# avr_board.net
KiCad netlist of a schematic drawn in EAGLE
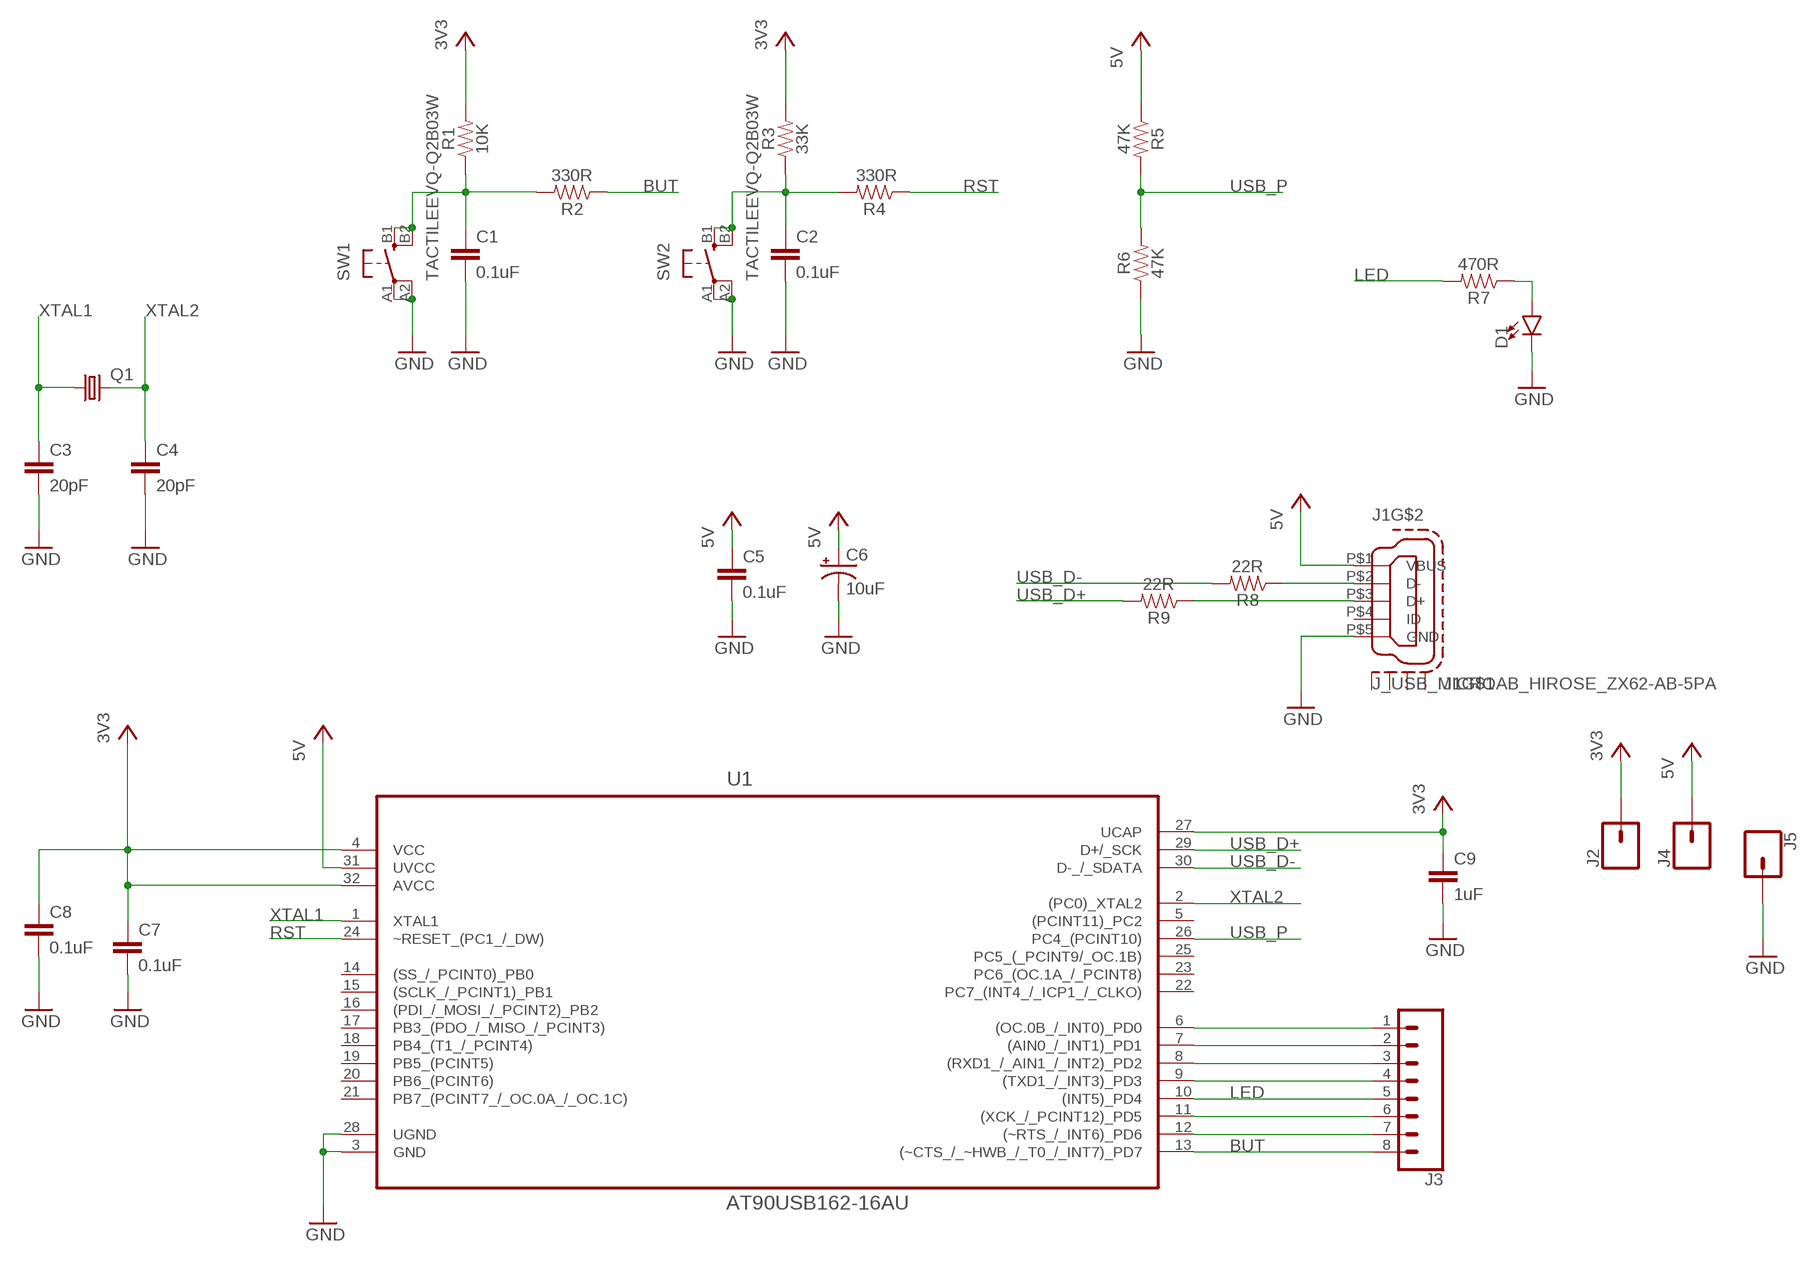
[diagram p0: schematic, sheet 1]

(export (version "E")
  (design (tool "Eeschema 10.0.6"))
  (components
    (comp (ref "C1")
      (value "0.1uF")
      (footprint "eagle-import:0603")
      (libsource (lib "eagle-import") (part "0.1UF-0603-25V-(+80/-20%)"))
    )
    (comp (ref "C2")
      (value "0.1uF")
      (footprint "eagle-import:0603")
      (libsource (lib "eagle-import") (part "0.1UF-0603-25V-(+80/-20%)"))
    )
    (comp (ref "C3")
      (value "20pF")
      (footprint "eagle-import:0603")
      (libsource (lib "eagle-import") (part "0.1UF-0603-25V-(+80/-20%)"))
    )
    (comp (ref "C4")
      (value "20pF")
      (footprint "eagle-import:0603")
      (libsource (lib "eagle-import") (part "0.1UF-0603-25V-(+80/-20%)"))
    )
    (comp (ref "C5")
      (value "0.1uF")
      (footprint "eagle-import:0603")
      (libsource (lib "eagle-import") (part "0.1UF-0603-25V-(+80/-20%)"))
    )
    (comp (ref "C6")
      (value "10uF")
      (footprint "eagle-import:EIA3216")
      (libsource (lib "eagle-import") (part "10UF-TANT"))
    )
    (comp (ref "C7")
      (value "0.1uF")
      (footprint "eagle-import:0603")
      (libsource (lib "eagle-import") (part "0.1UF-0603-25V-(+80/-20%)"))
    )
    (comp (ref "C8")
      (value "0.1uF")
      (footprint "eagle-import:0603")
      (libsource (lib "eagle-import") (part "0.1UF-0603-25V-(+80/-20%)"))
    )
    (comp (ref "C9")
      (value "1uF")
      (footprint "eagle-import:0603")
      (libsource (lib "eagle-import") (part "0.1UF-0603-25V-(+80/-20%)"))
    )
    (comp (ref "D1")
      (value "LEDPLCC")
      (footprint "eagle-import:PLCC-2")
      (libsource (lib "eagle-import") (part "LEDPLCC"))
    )
    (comp (ref "J1")
      (value "J_USB_MICROAB_HIROSE_ZX62-AB-5PA")
      (footprint "eagle-import:J_USB_MICROAB_HIROSE_ZX62-AB-5PA")
      (libsource (lib "eagle-import") (part "J_USB_MICROAB_HIROSE_ZX62-AB-5PA"))
    )
    (comp (ref "J2")
      (value "CONN_01")
      (footprint "eagle-import:1X01")
      (libsource (lib "eagle-import") (part "CONN_01"))
    )
    (comp (ref "J3")
      (value "CONN_08\"")
      (footprint "eagle-import:1X08")
      (libsource (lib "eagle-import") (part "CONN_08{dblquote}"))
    )
    (comp (ref "J4")
      (value "CONN_01")
      (footprint "eagle-import:1X01")
      (libsource (lib "eagle-import") (part "CONN_01"))
    )
    (comp (ref "J5")
      (value "CONN_01")
      (footprint "eagle-import:1X01")
      (libsource (lib "eagle-import") (part "CONN_01"))
    )
    (comp (ref "Q1")
      (value "CRYSTALCTS406")
      (footprint "eagle-import:CTS406")
      (libsource (lib "eagle-import") (part "CRYSTALCTS406"))
    )
    (comp (ref "R1")
      (value "10K")
      (footprint "eagle-import:0603")
      (libsource (lib "eagle-import") (part "RESISTOR0603"))
    )
    (comp (ref "R2")
      (value "330R")
      (footprint "eagle-import:0603")
      (libsource (lib "eagle-import") (part "RESISTOR0603"))
    )
    (comp (ref "R3")
      (value "33K")
      (footprint "eagle-import:0603")
      (libsource (lib "eagle-import") (part "RESISTOR0603"))
    )
    (comp (ref "R4")
      (value "330R")
      (footprint "eagle-import:0603")
      (libsource (lib "eagle-import") (part "RESISTOR0603"))
    )
    (comp (ref "R5")
      (value "47K")
      (footprint "eagle-import:0603")
      (libsource (lib "eagle-import") (part "RESISTOR0603"))
    )
    (comp (ref "R6")
      (value "47K")
      (footprint "eagle-import:0603")
      (libsource (lib "eagle-import") (part "RESISTOR0603"))
    )
    (comp (ref "R7")
      (value "470R")
      (footprint "eagle-import:0603")
      (libsource (lib "eagle-import") (part "RESISTOR0603"))
    )
    (comp (ref "R8")
      (value "22R")
      (footprint "eagle-import:0603")
      (libsource (lib "eagle-import") (part "RESISTOR0603"))
    )
    (comp (ref "R9")
      (value "22R")
      (footprint "eagle-import:0603")
      (libsource (lib "eagle-import") (part "RESISTOR0603"))
    )
    (comp (ref "SW1")
      (value "TACTILEEVQ-Q2B03W")
      (footprint "eagle-import:TACTILE_PAC")
      (libsource (lib "eagle-import") (part "TACTILEEVQ-Q2B03W"))
    )
    (comp (ref "SW2")
      (value "TACTILEEVQ-Q2B03W")
      (footprint "eagle-import:TACTILE_PAC")
      (libsource (lib "eagle-import") (part "TACTILEEVQ-Q2B03W"))
    )
    (comp (ref "U1")
      (value "AT90USB162-16AU")
      (footprint "eagle-import:QFP80P900X900X120-32N")
      (fields (field (name "MF") "Microchip"))
      (libsource (lib "eagle-import") (part "AT90USB162-16AU"))
    )
  )
  (nets
    (net (code "1") (name "/BUT") (class "Default")
      (node (ref "J3") (pin "8") (pinfunction "8_8") (pintype "passive"))
      (node (ref "R2") (pin "1") (pinfunction "1_1") (pintype "passive"))
      (node (ref "U1") (pin "13") (pinfunction "(~{CTS_/_}HWB_/_T0_/_INT7)_PD7_13") (pintype "bidirectional"))
    )
    (net (code "2") (name "/LED") (class "Default")
      (node (ref "J3") (pin "5") (pinfunction "5_5") (pintype "passive"))
      (node (ref "R7") (pin "2") (pinfunction "2_2") (pintype "passive"))
      (node (ref "U1") (pin "10") (pinfunction "(INT5)_PD4_10") (pintype "bidirectional"))
    )
    (net (code "3") (name "/RST") (class "Default")
      (node (ref "R4") (pin "1") (pinfunction "1_1") (pintype "passive"))
      (node (ref "U1") (pin "24") (pinfunction "~{RESET_(PC1_/_DW})_24") (pintype "bidirectional"))
    )
    (net (code "4") (name "/USB_D+") (class "Default")
      (node (ref "R9") (pin "2") (pinfunction "2_2") (pintype "passive"))
      (node (ref "U1") (pin "29") (pinfunction "D+/_SCK_29") (pintype "bidirectional"))
    )
    (net (code "5") (name "/USB_D-") (class "Default")
      (node (ref "R8") (pin "2") (pinfunction "2_2") (pintype "passive"))
      (node (ref "U1") (pin "30") (pinfunction "D-_/_SDATA_30") (pintype "bidirectional"))
    )
    (net (code "6") (name "/USB_P") (class "Default")
      (node (ref "R5") (pin "2") (pinfunction "2_2") (pintype "passive"))
      (node (ref "R6") (pin "2") (pinfunction "2_2") (pintype "passive"))
      (node (ref "U1") (pin "26") (pinfunction "PC4_(PCINT10)_26") (pintype "bidirectional"))
    )
    (net (code "7") (name "/XTAL1") (class "Default")
      (node (ref "C3") (pin "1") (pinfunction "1_1") (pintype "passive"))
      (node (ref "Q1") (pin "1") (pinfunction "1_1") (pintype "passive"))
      (node (ref "U1") (pin "1") (pinfunction "XTAL1_1") (pintype "input"))
    )
    (net (code "8") (name "/XTAL2") (class "Default")
      (node (ref "C4") (pin "1") (pinfunction "1_1") (pintype "passive"))
      (node (ref "Q1") (pin "3") (pinfunction "2_3") (pintype "passive"))
      (node (ref "U1") (pin "2") (pinfunction "(PC0)_XTAL2_2") (pintype "bidirectional"))
    )
    (net (code "9") (name "3V3") (class "Default")
      (node (ref "C7") (pin "1") (pinfunction "1_1") (pintype "passive"))
      (node (ref "C8") (pin "1") (pinfunction "1_1") (pintype "passive"))
      (node (ref "C9") (pin "1") (pinfunction "1_1") (pintype "passive"))
      (node (ref "J2") (pin "1") (pinfunction "1_1") (pintype "passive"))
      (node (ref "R1") (pin "2") (pinfunction "2_2") (pintype "passive"))
      (node (ref "R3") (pin "2") (pinfunction "2_2") (pintype "passive"))
      (node (ref "U1") (pin "27") (pinfunction "UCAP_27") (pintype "output"))
      (node (ref "U1") (pin "32") (pinfunction "AVCC_32") (pintype "power_in"))
      (node (ref "U1") (pin "4") (pinfunction "VCC_4") (pintype "power_in"))
    )
    (net (code "10") (name "5V") (class "Default")
      (node (ref "C5") (pin "1") (pinfunction "1_1") (pintype "passive"))
      (node (ref "C6") (pin "A") (pinfunction "+_A") (pintype "passive"))
      (node (ref "J1") (pin "P$1") (pinfunction "VBUS_P$1") (pintype "bidirectional"))
      (node (ref "J4") (pin "1") (pinfunction "1_1") (pintype "passive"))
      (node (ref "R5") (pin "1") (pinfunction "1_1") (pintype "passive"))
      (node (ref "U1") (pin "31") (pinfunction "UVCC_31") (pintype "power_in"))
    )
    (net (code "11") (name "GND") (class "Default")
      (node (ref "C1") (pin "2") (pinfunction "2_2") (pintype "passive"))
      (node (ref "C2") (pin "2") (pinfunction "2_2") (pintype "passive"))
      (node (ref "C3") (pin "2") (pinfunction "2_2") (pintype "passive"))
      (node (ref "C4") (pin "2") (pinfunction "2_2") (pintype "passive"))
      (node (ref "C5") (pin "2") (pinfunction "2_2") (pintype "passive"))
      (node (ref "C6") (pin "C") (pinfunction "-_C") (pintype "passive"))
      (node (ref "C7") (pin "2") (pinfunction "2_2") (pintype "passive"))
      (node (ref "C8") (pin "2") (pinfunction "2_2") (pintype "passive"))
      (node (ref "C9") (pin "2") (pinfunction "2_2") (pintype "passive"))
      (node (ref "D1") (pin "C") (pinfunction "C_C") (pintype "passive"))
      (node (ref "J1") (pin "P$5") (pinfunction "GND_P$5") (pintype "bidirectional"))
      (node (ref "J5") (pin "1") (pinfunction "1_1") (pintype "passive"))
      (node (ref "R6") (pin "1") (pinfunction "1_1") (pintype "passive"))
      (node (ref "SW1") (pin "A1") (pinfunction "PA1_A1") (pintype "passive"))
      (node (ref "SW1") (pin "A2") (pinfunction "PA2_A2") (pintype "passive"))
      (node (ref "SW2") (pin "A1") (pinfunction "PA1_A1") (pintype "passive"))
      (node (ref "SW2") (pin "A2") (pinfunction "PA2_A2") (pintype "passive"))
      (node (ref "U1") (pin "28") (pinfunction "UGND_28") (pintype "passive"))
      (node (ref "U1") (pin "3") (pinfunction "GND_3") (pintype "passive"))
    )
    (net (code "12") (name "Net-(D1-PadA)") (class "Default")
      (node (ref "D1") (pin "A") (pinfunction "A_A") (pintype "passive"))
      (node (ref "R7") (pin "1") (pinfunction "1_1") (pintype "passive"))
    )
    (net (code "13") (name "Net-(J1B-D+)") (class "Default")
      (node (ref "J1") (pin "P$3") (pinfunction "D+_P$3") (pintype "bidirectional"))
      (node (ref "R9") (pin "1") (pinfunction "1_1") (pintype "passive"))
    )
    (net (code "14") (name "Net-(J1B-D-)") (class "Default")
      (node (ref "J1") (pin "P$2") (pinfunction "D-_P$2") (pintype "bidirectional"))
      (node (ref "R8") (pin "1") (pinfunction "1_1") (pintype "passive"))
    )
    (net (code "15") (name "Net-(SW1-PB1)") (class "Default")
      (node (ref "C1") (pin "1") (pinfunction "1_1") (pintype "passive"))
      (node (ref "R1") (pin "1") (pinfunction "1_1") (pintype "passive"))
      (node (ref "R2") (pin "2") (pinfunction "2_2") (pintype "passive"))
      (node (ref "SW1") (pin "B1") (pinfunction "PB1_B1") (pintype "passive"))
      (node (ref "SW1") (pin "B2") (pinfunction "PB2_B2") (pintype "passive"))
    )
    (net (code "16") (name "Net-(SW2-PB1)") (class "Default")
      (node (ref "C2") (pin "1") (pinfunction "1_1") (pintype "passive"))
      (node (ref "R3") (pin "1") (pinfunction "1_1") (pintype "passive"))
      (node (ref "R4") (pin "2") (pinfunction "2_2") (pintype "passive"))
      (node (ref "SW2") (pin "B1") (pinfunction "PB1_B1") (pintype "passive"))
      (node (ref "SW2") (pin "B2") (pinfunction "PB2_B2") (pintype "passive"))
    )
    (net (code "17") (name "Net-(U1-(AIN0_{slash}_INT1)_PD1)") (class "Default")
      (node (ref "J3") (pin "2") (pinfunction "2_2") (pintype "passive"))
      (node (ref "U1") (pin "7") (pinfunction "(AIN0_/_INT1)_PD1_7") (pintype "bidirectional"))
    )
    (net (code "18") (name "Net-(U1-(OC.0B_{slash}_INT0)_PD0)") (class "Default")
      (node (ref "J3") (pin "1") (pinfunction "1_1") (pintype "passive"))
      (node (ref "U1") (pin "6") (pinfunction "(OC.0B_/_INT0)_PD0_6") (pintype "bidirectional"))
    )
    (net (code "19") (name "Net-(U1-(RXD1_{slash}_AIN1_{slash}_INT2)_PD2)") (class "Default")
      (node (ref "J3") (pin "3") (pinfunction "3_3") (pintype "passive"))
      (node (ref "U1") (pin "8") (pinfunction "(RXD1_/_AIN1_/_INT2)_PD2_8") (pintype "bidirectional"))
    )
    (net (code "20") (name "Net-(U1-(TXD1_{slash}_INT3)_PD3)") (class "Default")
      (node (ref "J3") (pin "4") (pinfunction "4_4") (pintype "passive"))
      (node (ref "U1") (pin "9") (pinfunction "(TXD1_/_INT3)_PD3_9") (pintype "bidirectional"))
    )
    (net (code "21") (name "Net-(U1-(XCK_{slash}_PCINT12)_PD5)") (class "Default")
      (node (ref "J3") (pin "6") (pinfunction "6_6") (pintype "passive"))
      (node (ref "U1") (pin "11") (pinfunction "(XCK_/_PCINT12)_PD5_11") (pintype "bidirectional"))
    )
    (net (code "22") (name "Net-(U1-(~{RTS_{slash}_INT6})_PD6)") (class "Default")
      (node (ref "J3") (pin "7") (pinfunction "7_7") (pintype "passive"))
      (node (ref "U1") (pin "12") (pinfunction "(~{RTS_/_INT6})_PD6_12") (pintype "bidirectional"))
    )
    (net (code "23") (name "unconnected-(J1A-S1-PadSHIELD1)") (class "Default")
      (node (ref "J1") (pin "SHIELD1") (pinfunction "S1_SHIELD1") (pintype "passive"))
    )
    (net (code "24") (name "unconnected-(J1A-S2-PadSHIELD2)") (class "Default")
      (node (ref "J1") (pin "SHIELD2") (pinfunction "S2_SHIELD2") (pintype "passive"))
    )
    (net (code "25") (name "unconnected-(J1A-S3-PadSHIELD3)") (class "Default")
      (node (ref "J1") (pin "SHIELD3") (pinfunction "S3_SHIELD3") (pintype "passive"))
    )
    (net (code "26") (name "unconnected-(J1A-S4-PadSHIELD4)") (class "Default")
      (node (ref "J1") (pin "SHIELD4") (pinfunction "S4_SHIELD4") (pintype "passive"))
    )
    (net (code "27") (name "unconnected-(J1B-ID-PadP$4)") (class "Default")
      (node (ref "J1") (pin "P$4") (pinfunction "ID_P$4") (pintype "bidirectional"))
    )
    (net (code "28") (name "unconnected-(U1-(PCINT11)_PC2-Pad5)") (class "Default")
      (node (ref "U1") (pin "5") (pinfunction "(PCINT11)_PC2_5") (pintype "bidirectional"))
    )
    (net (code "29") (name "unconnected-(U1-(PDI_{slash}_MOSI_{slash}_PCINT2)_PB2-Pad16)") (class "Default")
      (node (ref "U1") (pin "16") (pinfunction "(PDI_/_MOSI_/_PCINT2)_PB2_16") (pintype "bidirectional"))
    )
    (net (code "30") (name "unconnected-(U1-(SCLK_{slash}_PCINT1)_PB1-Pad15)") (class "Default")
      (node (ref "U1") (pin "15") (pinfunction "(SCLK_/_PCINT1)_PB1_15") (pintype "bidirectional"))
    )
    (net (code "31") (name "unconnected-(U1-(SS_{slash}_PCINT0)_PB0-Pad14)") (class "Default")
      (node (ref "U1") (pin "14") (pinfunction "(SS_/_PCINT0)_PB0_14") (pintype "bidirectional"))
    )
    (net (code "32") (name "unconnected-(U1-PB3_(PDO_{slash}_MISO_{slash}_PCINT3)-Pad17)") (class "Default")
      (node (ref "U1") (pin "17") (pinfunction "PB3_(PDO_/_MISO_/_PCINT3)_17") (pintype "bidirectional"))
    )
    (net (code "33") (name "unconnected-(U1-PB4_(T1_{slash}_PCINT4)-Pad18)") (class "Default")
      (node (ref "U1") (pin "18") (pinfunction "PB4_(T1_/_PCINT4)_18") (pintype "bidirectional"))
    )
    (net (code "34") (name "unconnected-(U1-PB5_(PCINT5)-Pad19)") (class "Default")
      (node (ref "U1") (pin "19") (pinfunction "PB5_(PCINT5)_19") (pintype "bidirectional"))
    )
    (net (code "35") (name "unconnected-(U1-PB6_(PCINT6)-Pad20)") (class "Default")
      (node (ref "U1") (pin "20") (pinfunction "PB6_(PCINT6)_20") (pintype "bidirectional"))
    )
    (net (code "36") (name "unconnected-(U1-PB7_(PCINT7_{slash}_OC.0A_{slash}_OC.1C)-Pad21)") (class "Default")
      (node (ref "U1") (pin "21") (pinfunction "PB7_(PCINT7_/_OC.0A_/_OC.1C)_21") (pintype "bidirectional"))
    )
    (net (code "37") (name "unconnected-(U1-PC5_(_PCINT9{slash}_OC.1B)-Pad25)") (class "Default")
      (node (ref "U1") (pin "25") (pinfunction "PC5_(_PCINT9/_OC.1B)_25") (pintype "bidirectional"))
    )
    (net (code "38") (name "unconnected-(U1-PC6_(OC.1A_{slash}_PCINT8)-Pad23)") (class "Default")
      (node (ref "U1") (pin "23") (pinfunction "PC6_(OC.1A_/_PCINT8)_23") (pintype "bidirectional"))
    )
    (net (code "39") (name "unconnected-(U1-PC7_(INT4_{slash}_ICP1_{slash}_CLKO)-Pad22)") (class "Default")
      (node (ref "U1") (pin "22") (pinfunction "PC7_(INT4_/_ICP1_/_CLKO)_22") (pintype "bidirectional"))
    )
  )
)
